# Final_Schematic_PCB.net
KiCad netlist of a schematic drawn in EAGLE
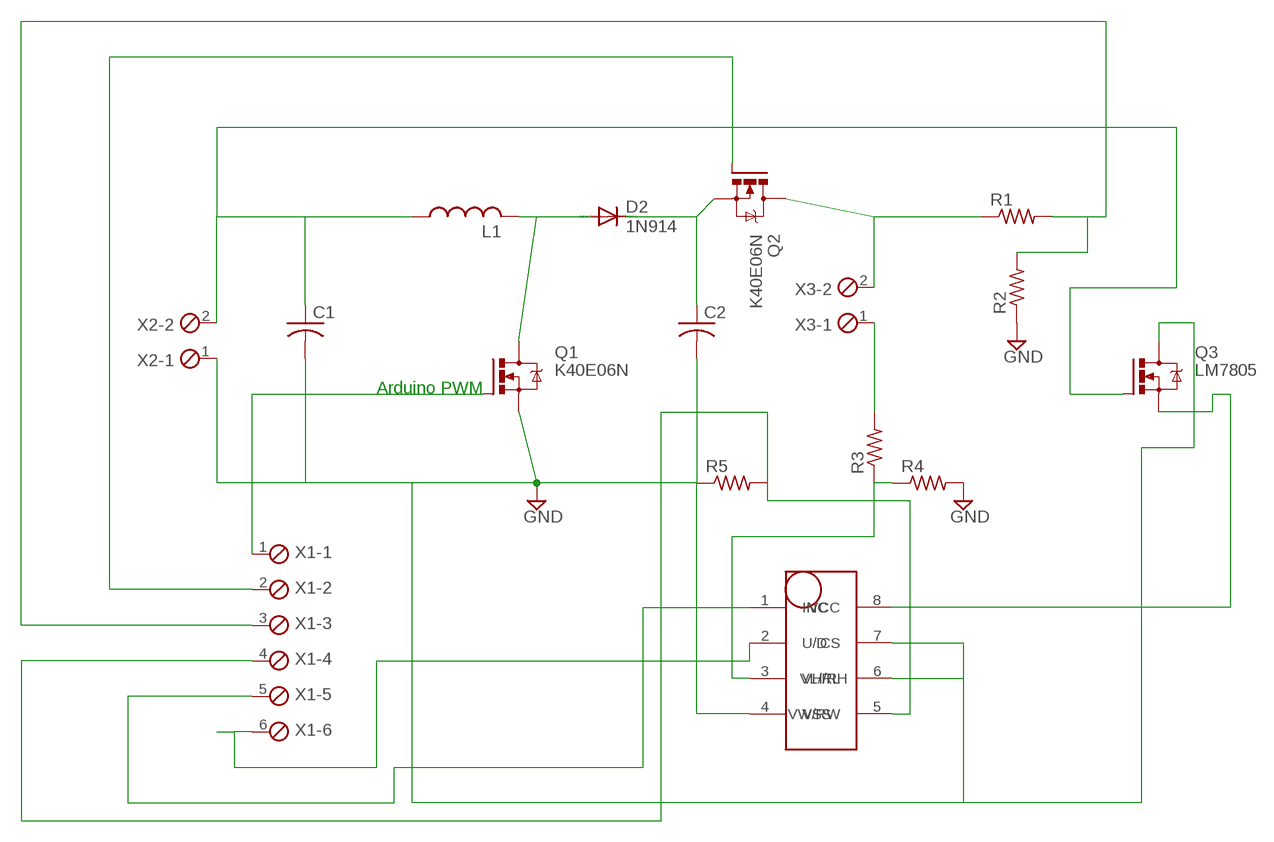
[diagram p0: schematic, sheet 1]

(export (version "E")
  (design (tool "Eeschema 10.0.6"))
  (components
    (comp (ref "C1")
      (value "C-US050-045X075")
      (footprint "eagle-import:C050-045X075")
      (libsource (lib "eagle-import") (part "C-US050-045X075"))
    )
    (comp (ref "C2")
      (value "C-US050-045X075")
      (footprint "eagle-import:C050-045X075")
      (libsource (lib "eagle-import") (part "C-US050-045X075"))
    )
    (comp (ref "D2")
      (value "1N914")
      (footprint "eagle-import:DO41-10")
      (libsource (lib "eagle-import") (part "1N4933"))
    )
    (comp (ref "L1")
      (value "L-US0207/5V")
      (footprint "eagle-import:0207_5V")
      (libsource (lib "eagle-import") (part "L-US0207/5V"))
    )
    (comp (ref "Q1")
      (value "K40E06N")
      (footprint "eagle-import:TO220BV")
      (libsource (lib "eagle-import") (part "IRF530"))
    )
    (comp (ref "Q2")
      (value "K40E06N")
      (footprint "eagle-import:TO220BV")
      (libsource (lib "eagle-import") (part "IRF530"))
    )
    (comp (ref "Q3")
      (value "LM7805")
      (footprint "eagle-import:TO220BV")
      (libsource (lib "eagle-import") (part "IRF530"))
    )
    (comp (ref "R1")
      (value "R-US_0204/5")
      (footprint "eagle-import:0204_5")
      (libsource (lib "eagle-import") (part "R-US_0204/5"))
    )
    (comp (ref "R2")
      (value "R-US_0204/5")
      (footprint "eagle-import:0204_5")
      (libsource (lib "eagle-import") (part "R-US_0204/5"))
    )
    (comp (ref "R3")
      (value "R-US_0204/5")
      (footprint "eagle-import:0204_5")
      (libsource (lib "eagle-import") (part "R-US_0204/5"))
    )
    (comp (ref "R4")
      (value "R-US_0204/5")
      (footprint "eagle-import:0204_5")
      (libsource (lib "eagle-import") (part "R-US_0204/5"))
    )
    (comp (ref "R5")
      (value "R-US_0204/5")
      (footprint "eagle-import:0204_5")
      (libsource (lib "eagle-import") (part "R-US_0204/5"))
    )
    (comp (ref "U$1")
      (value "1KDP")
      (footprint "eagle-import:1KDP")
      (libsource (lib "eagle-import") (part "1KDP"))
    )
    (comp (ref "X1")
      (value "MPT6")
      (footprint "eagle-import:6POL254")
      (libsource (lib "eagle-import") (part "MPT6"))
    )
    (comp (ref "X2")
      (value "MPT2")
      (footprint "eagle-import:2POL254")
      (libsource (lib "eagle-import") (part "MPT2"))
    )
    (comp (ref "X3")
      (value "MPT2")
      (footprint "eagle-import:2POL254")
      (libsource (lib "eagle-import") (part "MPT2"))
    )
  )
  (nets
    (net (code "1") (name "GND") (class "Default")
      (node (ref "C1") (pin "2") (pinfunction "2_2") (pintype "passive"))
      (node (ref "C2") (pin "2") (pinfunction "2_2") (pintype "passive"))
      (node (ref "Q1") (pin "S") (pinfunction "S_S") (pintype "passive"))
      (node (ref "Q3") (pin "D") (pinfunction "D_D") (pintype "passive"))
      (node (ref "R2") (pin "1") (pinfunction "1_1") (pintype "passive"))
      (node (ref "R4") (pin "2") (pinfunction "2_2") (pintype "passive"))
      (node (ref "R5") (pin "1") (pinfunction "1_1") (pintype "passive"))
      (node (ref "U$1") (pin "4") (pinfunction "VSS_4") (pintype "bidirectional"))
      (node (ref "U$1") (pin "6") (pinfunction "VL/RL_6") (pintype "bidirectional"))
      (node (ref "U$1") (pin "7") (pinfunction "CS_7") (pintype "bidirectional"))
      (node (ref "X2") (pin "1") (pinfunction "1_1") (pintype "passive"))
    )
    (net (code "2") (name "Net-(C2-Pad1)") (class "Default")
      (node (ref "C2") (pin "1") (pinfunction "1_1") (pintype "passive"))
      (node (ref "D2") (pin "C") (pinfunction "C_C") (pintype "passive"))
      (node (ref "Q2") (pin "S") (pinfunction "S_S") (pintype "passive"))
    )
    (net (code "3") (name "Net-(D2-PadA)") (class "Default")
      (node (ref "D2") (pin "A") (pinfunction "A_A") (pintype "passive"))
      (node (ref "L1") (pin "2") (pinfunction "2_2") (pintype "passive"))
      (node (ref "Q1") (pin "D") (pinfunction "D_D") (pintype "passive"))
    )
    (net (code "4") (name "Net-(Q1-PadG)") (class "Default")
      (node (ref "Q1") (pin "G") (pinfunction "G_G") (pintype "passive"))
      (node (ref "X1") (pin "1") (pinfunction "1_1") (pintype "passive"))
    )
    (net (code "5") (name "Net-(R3-Pad2)") (class "Default")
      (node (ref "R3") (pin "2") (pinfunction "2_2") (pintype "passive"))
      (node (ref "X3") (pin "1") (pinfunction "1_1") (pintype "passive"))
    )
    (net (code "6") (name "Net-(U$1-INC)") (class "Default")
      (node (ref "U$1") (pin "1") (pinfunction "INC_1") (pintype "bidirectional"))
      (node (ref "X1") (pin "5") (pinfunction "1_5") (pintype "passive"))
    )
    (net (code "7") (name "Net-(U$1-U{slash}D)") (class "Default")
      (node (ref "U$1") (pin "2") (pinfunction "U/D_2") (pintype "bidirectional"))
      (node (ref "X1") (pin "6") (pinfunction "1_6") (pintype "passive"))
    )
    (net (code "8") (name "Net-(U$1-VCC)") (class "Default")
      (node (ref "Q3") (pin "S") (pinfunction "S_S") (pintype "passive"))
      (node (ref "U$1") (pin "8") (pinfunction "VCC_8") (pintype "bidirectional"))
    )
    (net (code "9") (name "Net-(U$1-VH{slash}RH)") (class "Default")
      (node (ref "R3") (pin "1") (pinfunction "1_1") (pintype "passive"))
      (node (ref "R4") (pin "1") (pinfunction "1_1") (pintype "passive"))
      (node (ref "U$1") (pin "3") (pinfunction "VH/RH_3") (pintype "bidirectional"))
    )
    (net (code "10") (name "Net-(U$1-VW{slash}RW)") (class "Default")
      (node (ref "R5") (pin "2") (pinfunction "2_2") (pintype "passive"))
      (node (ref "U$1") (pin "5") (pinfunction "VW/RW_5") (pintype "bidirectional"))
      (node (ref "X1") (pin "4") (pinfunction "1_4") (pintype "passive"))
    )
    (net (code "11") (name "Net-(X1B-1)") (class "Default")
      (node (ref "Q2") (pin "G") (pinfunction "G_G") (pintype "passive"))
      (node (ref "X1") (pin "2") (pinfunction "1_2") (pintype "passive"))
    )
    (net (code "12") (name "Net-(X1C-1)") (class "Default")
      (node (ref "R1") (pin "2") (pinfunction "2_2") (pintype "passive"))
      (node (ref "R2") (pin "2") (pinfunction "2_2") (pintype "passive"))
      (node (ref "X1") (pin "3") (pinfunction "1_3") (pintype "passive"))
    )
    (net (code "13") (name "Net-(X2B-1)") (class "Default")
      (node (ref "C1") (pin "1") (pinfunction "1_1") (pintype "passive"))
      (node (ref "L1") (pin "1") (pinfunction "1_1") (pintype "passive"))
      (node (ref "Q3") (pin "G") (pinfunction "G_G") (pintype "passive"))
      (node (ref "X2") (pin "2") (pinfunction "1_2") (pintype "passive"))
    )
    (net (code "14") (name "Net-(X3B-1)") (class "Default")
      (node (ref "Q2") (pin "D") (pinfunction "D_D") (pintype "passive"))
      (node (ref "R1") (pin "1") (pinfunction "1_1") (pintype "passive"))
      (node (ref "X3") (pin "2") (pinfunction "1_2") (pintype "passive"))
    )
  )
)
